# Processor.net
KiCad netlist of a schematic drawn in Altium Designer
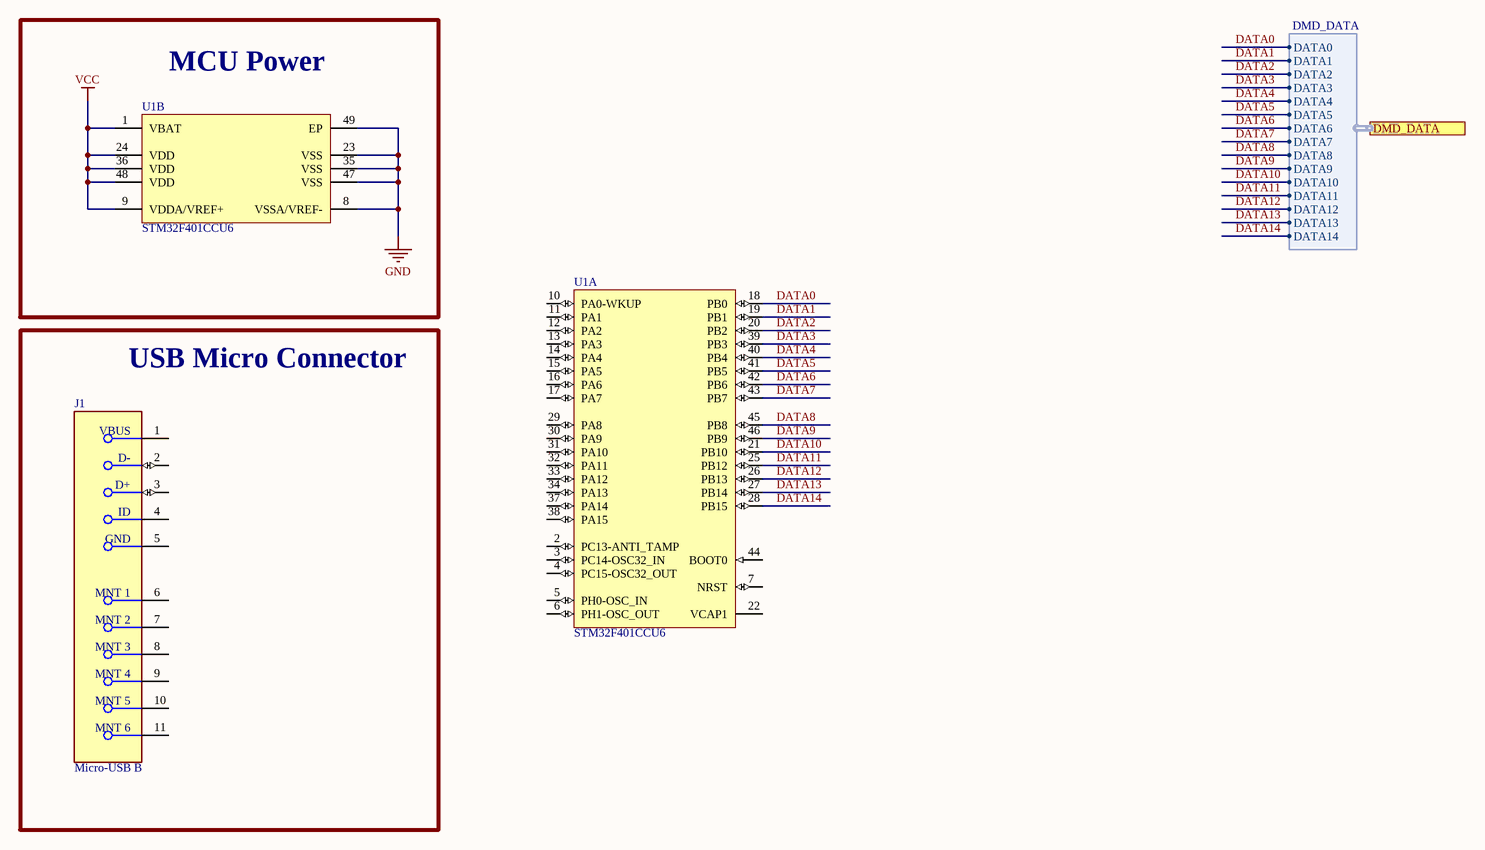
[diagram p0: Processor.SchDoc]

(export (version "E")
  (design (tool "Eeschema 10.0.6"))
  (components
    (comp (ref "J1")
      (value "Micro-USB B")
      (description "Micro-USB B Receptacle with Flange, Bottom Mount, Surface Mount, Lead-Free")
      (fields (field (name "MANUFACTURER") "Molex") (field (name "MANUFACTURER PART NUMBER") "47346-0001"))
      (libsource (lib "afra") (part "47346-0001"))
    )
    (comp (ref "U1")
      (value "STM32F401CCU6")
      (footprint "STM-UFQFPN48_N")
      (fields (field (name "MANUFACTURER") "STMicroelectronics"))
      (libsource (lib "afra") (part "STM32F401CCU6"))
    )
  )
  (nets
    (net (code "2") (name "/DATA0") (class "Default")
      (node (ref "U1") (pin "18") (pinfunction "PB0_18") (pintype "bidirectional"))
    )
    (net (code "3") (name "/DATA1") (class "Default")
      (node (ref "U1") (pin "19") (pinfunction "PB1_19") (pintype "bidirectional"))
    )
    (net (code "4") (name "/DATA2") (class "Default")
      (node (ref "U1") (pin "20") (pinfunction "PB2_20") (pintype "bidirectional"))
    )
    (net (code "5") (name "/DATA3") (class "Default")
      (node (ref "U1") (pin "39") (pinfunction "PB3_39") (pintype "bidirectional"))
    )
    (net (code "6") (name "/DATA4") (class "Default")
      (node (ref "U1") (pin "40") (pinfunction "PB4_40") (pintype "bidirectional"))
    )
    (net (code "7") (name "/DATA5") (class "Default")
      (node (ref "U1") (pin "41") (pinfunction "PB5_41") (pintype "bidirectional"))
    )
    (net (code "8") (name "/DATA6") (class "Default")
      (node (ref "U1") (pin "42") (pinfunction "PB6_42") (pintype "bidirectional"))
    )
    (net (code "9") (name "/DATA7") (class "Default")
      (node (ref "U1") (pin "43") (pinfunction "PB7_43") (pintype "bidirectional"))
    )
    (net (code "10") (name "/DATA8") (class "Default")
      (node (ref "U1") (pin "45") (pinfunction "PB8_45") (pintype "bidirectional"))
    )
    (net (code "11") (name "/DATA9") (class "Default")
      (node (ref "U1") (pin "46") (pinfunction "PB9_46") (pintype "bidirectional"))
    )
    (net (code "12") (name "/DATA10") (class "Default")
      (node (ref "U1") (pin "21") (pinfunction "PB10_21") (pintype "bidirectional"))
    )
    (net (code "13") (name "/DATA11") (class "Default")
      (node (ref "U1") (pin "25") (pinfunction "PB12_25") (pintype "bidirectional"))
    )
    (net (code "14") (name "/DATA12") (class "Default")
      (node (ref "U1") (pin "26") (pinfunction "PB13_26") (pintype "bidirectional"))
    )
    (net (code "15") (name "/DATA13") (class "Default")
      (node (ref "U1") (pin "27") (pinfunction "PB14_27") (pintype "bidirectional"))
    )
    (net (code "16") (name "/DATA14") (class "Default")
      (node (ref "U1") (pin "28") (pinfunction "PB15_28") (pintype "bidirectional"))
    )
    (net (code "18") (name "GND") (class "Default")
      (node (ref "U1") (pin "23") (pinfunction "VSS_23") (pintype "power_in"))
      (node (ref "U1") (pin "35") (pinfunction "VSS_35") (pintype "power_in"))
      (node (ref "U1") (pin "47") (pinfunction "VSS_47") (pintype "power_in"))
      (node (ref "U1") (pin "49") (pinfunction "EP_49") (pintype "power_in"))
      (node (ref "U1") (pin "8") (pinfunction "VSSA/VREF-_8") (pintype "power_in"))
    )
    (net (code "19") (name "VCC") (class "Default")
      (node (ref "U1") (pin "1") (pinfunction "VBAT_1") (pintype "power_in"))
      (node (ref "U1") (pin "24") (pinfunction "VDD_24") (pintype "power_in"))
      (node (ref "U1") (pin "36") (pinfunction "VDD_36") (pintype "power_in"))
      (node (ref "U1") (pin "48") (pinfunction "VDD_48") (pintype "power_in"))
      (node (ref "U1") (pin "9") (pinfunction "VDDA/VREF+_9") (pintype "power_in"))
    )
    (net (code "20") (name "unconnected-(J1-D+-Pad3)") (class "Default")
      (node (ref "J1") (pin "3") (pinfunction "D+_3") (pintype "bidirectional"))
    )
    (net (code "21") (name "unconnected-(J1-D--Pad2)") (class "Default")
      (node (ref "J1") (pin "2") (pinfunction "D-_2") (pintype "bidirectional"))
    )
    (net (code "22") (name "unconnected-(J1-GND-Pad5)") (class "Default")
      (node (ref "J1") (pin "5") (pinfunction "GND_5") (pintype "power_in"))
    )
    (net (code "23") (name "unconnected-(J1-ID-Pad4)") (class "Default")
      (node (ref "J1") (pin "4") (pinfunction "ID_4") (pintype "passive"))
    )
    (net (code "24") (name "unconnected-(J1-MNT_1-Pad6)") (class "Default")
      (node (ref "J1") (pin "6") (pinfunction "MNT_1_6") (pintype "passive"))
    )
    (net (code "25") (name "unconnected-(J1-MNT_2-Pad7)") (class "Default")
      (node (ref "J1") (pin "7") (pinfunction "MNT_2_7") (pintype "passive"))
    )
    (net (code "26") (name "unconnected-(J1-MNT_3-Pad8)") (class "Default")
      (node (ref "J1") (pin "8") (pinfunction "MNT_3_8") (pintype "passive"))
    )
    (net (code "27") (name "unconnected-(J1-MNT_4-Pad9)") (class "Default")
      (node (ref "J1") (pin "9") (pinfunction "MNT_4_9") (pintype "passive"))
    )
    (net (code "28") (name "unconnected-(J1-MNT_5-Pad10)") (class "Default")
      (node (ref "J1") (pin "10") (pinfunction "MNT_5_10") (pintype "passive"))
    )
    (net (code "29") (name "unconnected-(J1-MNT_6-Pad11)") (class "Default")
      (node (ref "J1") (pin "11") (pinfunction "MNT_6_11") (pintype "passive"))
    )
    (net (code "30") (name "unconnected-(J1-VBUS-Pad1)") (class "Default")
      (node (ref "J1") (pin "1") (pinfunction "VBUS_1") (pintype "power_in"))
    )
    (net (code "31") (name "unconnected-(U1A-BOOT0-Pad44)") (class "Default")
      (node (ref "U1") (pin "44") (pinfunction "BOOT0_44") (pintype "input"))
    )
    (net (code "32") (name "unconnected-(U1A-NRST-Pad7)") (class "Default")
      (node (ref "U1") (pin "7") (pinfunction "NRST_7") (pintype "bidirectional"))
    )
    (net (code "33") (name "unconnected-(U1A-PA0-WKUP-Pad10)") (class "Default")
      (node (ref "U1") (pin "10") (pinfunction "PA0-WKUP_10") (pintype "bidirectional"))
    )
    (net (code "34") (name "unconnected-(U1A-PA1-Pad11)") (class "Default")
      (node (ref "U1") (pin "11") (pinfunction "PA1_11") (pintype "bidirectional"))
    )
    (net (code "35") (name "unconnected-(U1A-PA2-Pad12)") (class "Default")
      (node (ref "U1") (pin "12") (pinfunction "PA2_12") (pintype "bidirectional"))
    )
    (net (code "36") (name "unconnected-(U1A-PA3-Pad13)") (class "Default")
      (node (ref "U1") (pin "13") (pinfunction "PA3_13") (pintype "bidirectional"))
    )
    (net (code "37") (name "unconnected-(U1A-PA4-Pad14)") (class "Default")
      (node (ref "U1") (pin "14") (pinfunction "PA4_14") (pintype "bidirectional"))
    )
    (net (code "38") (name "unconnected-(U1A-PA5-Pad15)") (class "Default")
      (node (ref "U1") (pin "15") (pinfunction "PA5_15") (pintype "bidirectional"))
    )
    (net (code "39") (name "unconnected-(U1A-PA6-Pad16)") (class "Default")
      (node (ref "U1") (pin "16") (pinfunction "PA6_16") (pintype "bidirectional"))
    )
    (net (code "40") (name "unconnected-(U1A-PA7-Pad17)") (class "Default")
      (node (ref "U1") (pin "17") (pinfunction "PA7_17") (pintype "bidirectional"))
    )
    (net (code "41") (name "unconnected-(U1A-PA8-Pad29)") (class "Default")
      (node (ref "U1") (pin "29") (pinfunction "PA8_29") (pintype "bidirectional"))
    )
    (net (code "42") (name "unconnected-(U1A-PA9-Pad30)") (class "Default")
      (node (ref "U1") (pin "30") (pinfunction "PA9_30") (pintype "bidirectional"))
    )
    (net (code "43") (name "unconnected-(U1A-PA10-Pad31)") (class "Default")
      (node (ref "U1") (pin "31") (pinfunction "PA10_31") (pintype "bidirectional"))
    )
    (net (code "44") (name "unconnected-(U1A-PA11-Pad32)") (class "Default")
      (node (ref "U1") (pin "32") (pinfunction "PA11_32") (pintype "bidirectional"))
    )
    (net (code "45") (name "unconnected-(U1A-PA12-Pad33)") (class "Default")
      (node (ref "U1") (pin "33") (pinfunction "PA12_33") (pintype "bidirectional"))
    )
    (net (code "46") (name "unconnected-(U1A-PA13-Pad34)") (class "Default")
      (node (ref "U1") (pin "34") (pinfunction "PA13_34") (pintype "bidirectional"))
    )
    (net (code "47") (name "unconnected-(U1A-PA14-Pad37)") (class "Default")
      (node (ref "U1") (pin "37") (pinfunction "PA14_37") (pintype "bidirectional"))
    )
    (net (code "48") (name "unconnected-(U1A-PA15-Pad38)") (class "Default")
      (node (ref "U1") (pin "38") (pinfunction "PA15_38") (pintype "bidirectional"))
    )
    (net (code "49") (name "unconnected-(U1A-PC13-ANTI_TAMP-Pad2)") (class "Default")
      (node (ref "U1") (pin "2") (pinfunction "PC13-ANTI_TAMP_2") (pintype "bidirectional"))
    )
    (net (code "50") (name "unconnected-(U1A-PC14-OSC32_IN-Pad3)") (class "Default")
      (node (ref "U1") (pin "3") (pinfunction "PC14-OSC32_IN_3") (pintype "bidirectional"))
    )
    (net (code "51") (name "unconnected-(U1A-PC15-OSC32_OUT-Pad4)") (class "Default")
      (node (ref "U1") (pin "4") (pinfunction "PC15-OSC32_OUT_4") (pintype "bidirectional"))
    )
    (net (code "52") (name "unconnected-(U1A-PH0-OSC_IN-Pad5)") (class "Default")
      (node (ref "U1") (pin "5") (pinfunction "PH0-OSC_IN_5") (pintype "bidirectional"))
    )
    (net (code "53") (name "unconnected-(U1A-PH1-OSC_OUT-Pad6)") (class "Default")
      (node (ref "U1") (pin "6") (pinfunction "PH1-OSC_OUT_6") (pintype "bidirectional"))
    )
    (net (code "54") (name "unconnected-(U1A-VCAP1-Pad22)") (class "Default")
      (node (ref "U1") (pin "22") (pinfunction "VCAP1_22") (pintype "power_in"))
    )
  )
)
